# IR_INPUT_POWER.net
KiCad netlist of a schematic drawn in Altium Designer
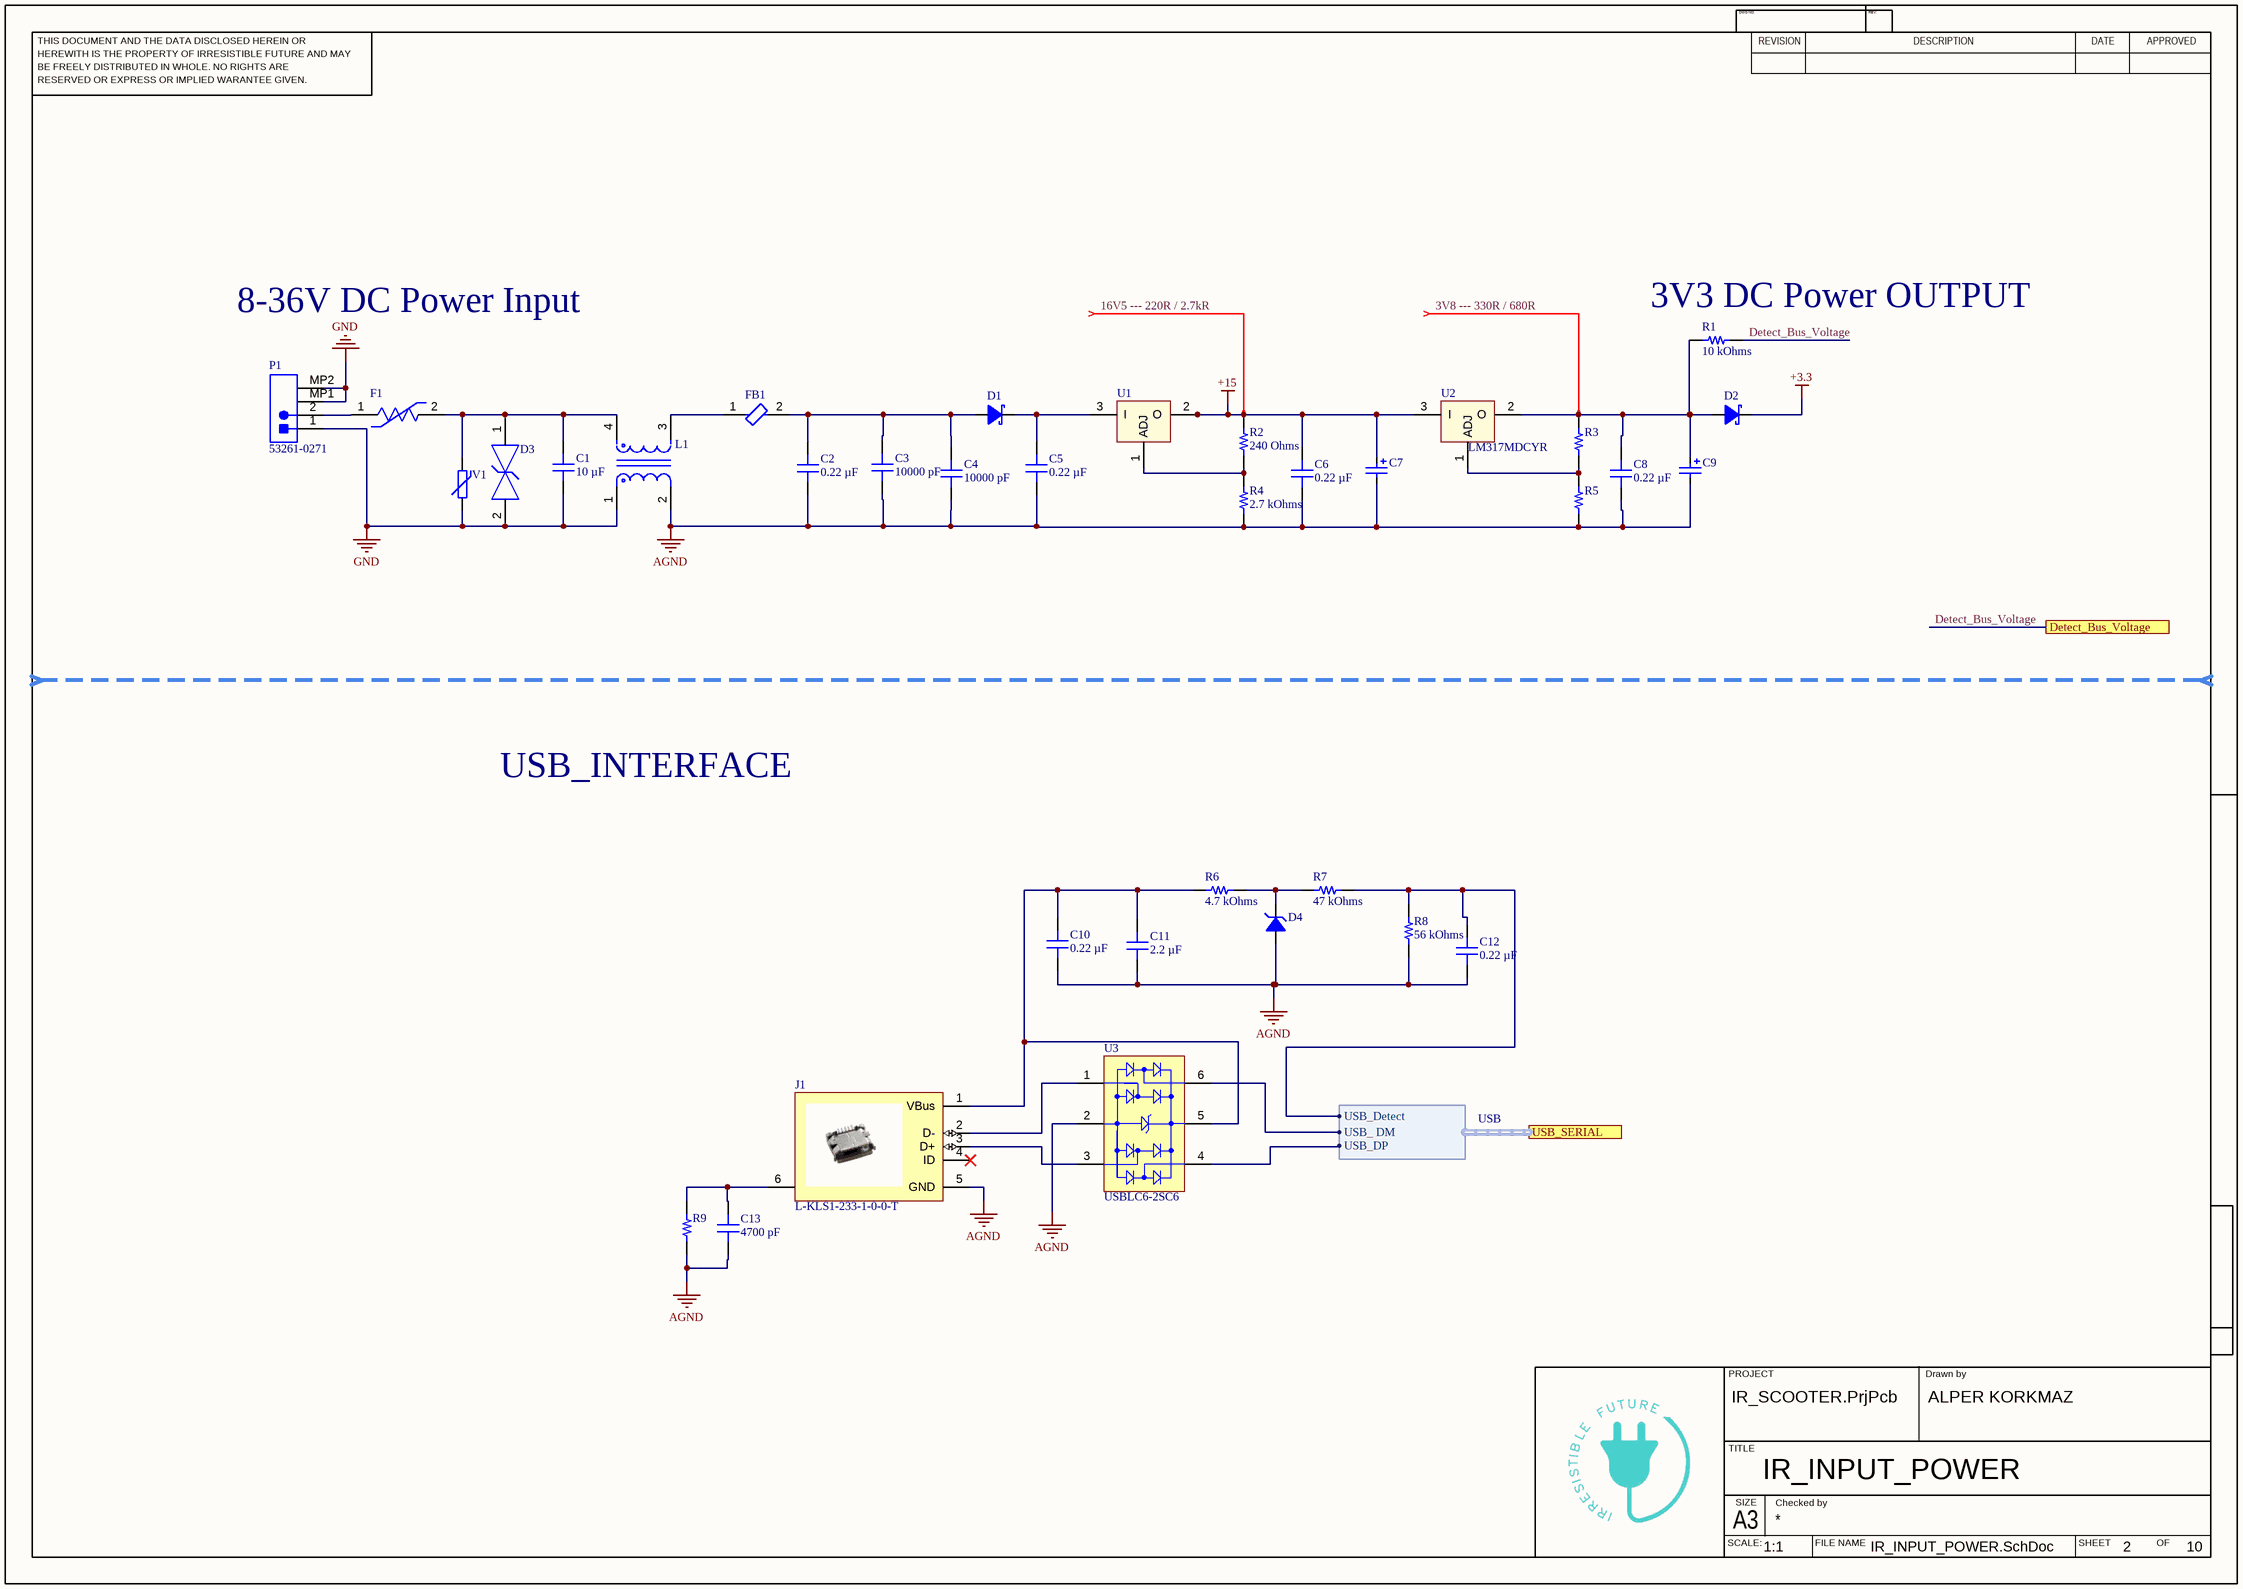
[diagram p0: IR_INPUT_POWER.SchDoc]

(export (version "E")
  (design (tool "Eeschema 10.0.6"))
  (components
    (comp (ref "C1")
      (value "10 µF")
      (footprint "CAP 1206_3216 - 0.8MM")
      (description "CAP CER 10UF 16V X5R 1206")
      (fields (field (name "PART NUMBER") "EMK316BJ106MD-T") (field (name "MANUFACTURER") "Taiyo Yuden"))
      (libsource (lib "Celestial Altium Library - altium_library") (part "Capacitor"))
    )
    (comp (ref "C2")
      (value "0.22 µF")
      (footprint "CAP 0805_2012")
      (description "CAP CER 0.22UF 100V X7R 0805")
      (fields (field (name "PART NUMBER") "HMJ212BB7224KGHT") (field (name "MANUFACTURER") "Taiyo Yuden"))
      (libsource (lib "Celestial Altium Library - altium_library") (part "Capacitor"))
    )
    (comp (ref "C3")
      (value "10000 pF")
      (footprint "CAP 0805_2012")
      (description "CAP CER 0805 10NF 100V X7R")
      (fields (field (name "PART NUMBER") "C0805X103K1RAC3316") (field (name "MANUFACTURER") "KEMET"))
      (libsource (lib "Celestial Altium Library - altium_library") (part "Capacitor"))
    )
    (comp (ref "C4")
      (value "10000 pF")
      (footprint "CAP 0805_2012")
      (description "CAP CER SMD 0805 .01UF X7R 5% 50")
      (fields (field (name "PART NUMBER") "C0805C103J5RAC7210") (field (name "MANUFACTURER") "KEMET"))
      (libsource (lib "Celestial Altium Library - altium_library") (part "Capacitor"))
    )
    (comp (ref "C5")
      (value "0.22 µF")
      (footprint "CAP 0805_2012")
      (description "CAP CER 0.22UF 100V X7R 0805")
      (fields (field (name "PART NUMBER") "HMJ212BB7224KGHT") (field (name "MANUFACTURER") "Taiyo Yuden"))
      (libsource (lib "Celestial Altium Library - altium_library") (part "Capacitor"))
    )
    (comp (ref "C6")
      (value "0.22 µF")
      (footprint "CAP 0805_2012")
      (description "CAP CER 0.22UF 100V X7R 0805")
      (fields (field (name "PART NUMBER") "HMJ212BB7224KGHT") (field (name "MANUFACTURER") "Taiyo Yuden"))
      (libsource (lib "Celestial Altium Library - altium_library") (part "Capacitor"))
    )
    (comp (ref "C7")
      (value "EEE-1VA101XP")
      (footprint "AE_C_R6")
      (description "CAP ALUM 100UF 20% 35V SMD")
      (fields
        (field (name "TOLERANCE") "±20%")
        (field (name "MANUFACTURER") "Panasonic Electronic Components")
      )
      (libsource (lib "Altium_Lib") (part "Capacitor_(Electrolytic)__EEE-1VA101XP"))
    )
    (comp (ref "C8")
      (value "0.22 µF")
      (footprint "CAP 0805_2012")
      (description "CAP CER 0.22UF 100V X7R 0805")
      (fields (field (name "PART NUMBER") "HMJ212BB7224KGHT") (field (name "MANUFACTURER") "Taiyo Yuden"))
      (libsource (lib "Celestial Altium Library - altium_library") (part "Capacitor"))
    )
    (comp (ref "C9")
      (value "EEE-1VA101XP")
      (footprint "AE_C_R6")
      (description "CAP ALUM 100UF 20% 35V SMD")
      (fields
        (field (name "TOLERANCE") "±20%")
        (field (name "MANUFACTURER") "Panasonic Electronic Components")
      )
      (libsource (lib "Altium_Lib") (part "Capacitor_(Electrolytic)__EEE-1VA101XP"))
    )
    (comp (ref "C10")
      (value "0.22 µF")
      (footprint "CAP 0805_2012")
      (description "CAP CER 0.22UF 100V X7R 0805")
      (fields (field (name "PART NUMBER") "HMJ212BB7224KGHT") (field (name "MANUFACTURER") "Taiyo Yuden"))
      (libsource (lib "Celestial Altium Library - altium_library") (part "Capacitor"))
    )
    (comp (ref "C11")
      (value "2.2 µF")
      (footprint "CAP 0805_2012")
      (description "CAP CER 2.2UF 50V X5R 0805")
      (fields
        (field (name "PART NUMBER") "CL21A225KB9LNNC")
        (field (name "MANUFACTURER") "Samsung Electro-Mechanics")
      )
      (libsource (lib "Celestial Altium Library - altium_library") (part "Capacitor"))
    )
    (comp (ref "C12")
      (value "0.22 µF")
      (footprint "CAP 0805_2012")
      (description "CAP CER 0.22UF 100V X7R 0805")
      (fields (field (name "PART NUMBER") "HMJ212BB7224KGHT") (field (name "MANUFACTURER") "Taiyo Yuden"))
      (libsource (lib "Celestial Altium Library - altium_library") (part "Capacitor"))
    )
    (comp (ref "C13")
      (value "4700 pF")
      (footprint "CAP 0805_2012")
      (description "CAP CER 4700PF 50V X7R 0805")
      (fields (field (name "PART NUMBER") "C0805C472K5RACAUTO") (field (name "MANUFACTURER") "KEMET"))
      (libsource (lib "Celestial Altium Library - altium_library") (part "Capacitor"))
    )
    (comp (ref "D1")
      (value "PMEG6020ELRX")
      (footprint "SOD123W")
      (description "DIODE SCHOTTKY 60V 2A CFP3")
      (fields (field (name "MANUFACTURER") "Nexperia"))
      (libsource (lib "Altium_Lib") (part "DIODE_PMEG6020ELRX"))
    )
    (comp (ref "D2")
      (value "PMEG6020ELRX")
      (footprint "SOD123W")
      (description "DIODE SCHOTTKY 60V 2A CFP3")
      (fields (field (name "MANUFACTURER") "Nexperia"))
      (libsource (lib "Altium_Lib") (part "DIODE_PMEG6020ELRX"))
    )
    (comp (ref "D3")
      (value "SMAJ5.0CA-TR")
      (footprint "FP-SMA-MFG")
      (description "TVS DIODE 5V 13.4V SMA")
      (fields
        (field (name "MANUFACTURER") "STMicroelectronics")
        (field (name "OCTOPART") "https://octopart.com/smaj5.0ca-tr-stmicroelectronics-350177")
      )
      (libsource (lib "Altium Content Vault") (part "876f4347bf90aa6f500f43e3cd03972"))
    )
    (comp (ref "D4")
      (value "BZT52C5V6-HE3-08")
      (footprint "SOD123")
      (description "DIODE ZENER 5.6V 410MW SOD123")
      (fields (field (name "MANUFACTURER") "Vishay") (field (name "TOLERANCE") "5%"))
      (libsource (lib "Altium_Lib") (part "DIODE_BZT52C5V6-HE3-08"))
    )
    (comp (ref "F1")
      (value "1812L075/33DR")
      (footprint "FP-1812L075-33DR-MFG")
      (description "PTC RESET FUSE 33V 750MA 1812")
      (libsource (lib "Altium Content Vault") (part "fdf083d5f6389a9a1c4e51137f46658"))
    )
    (comp (ref "FB1")
      (value "BLM21PG220SN1D")
      (footprint "FP-BLM21-0_2-t0_85-e0_5-MFG")
      (description "Chip Ferrite Bead, 0805, 22Ω @ 100MHz, 0.009Ω, 25%, 6A")
      (fields (field (name "TOLERANCE") "25%"))
      (libsource (lib "Altium Content Vault") (part "5f30dd21d616792df468990f7003faa"))
    )
    (comp (ref "J1")
      (value "L-KLS1-233-1-0-0-T")
      (footprint "USB_MICRO_1981584-1")
      (description "Conn Micro USB 2.0 Type AB RCP 5 POS 0.65mm Solder RA SMD 5 Terminal 1 Port T/R")
      (fields (field (name "MANUFACTURER") "KLS Electronic"))
      (libsource (lib "Altium_Lib") (part "USB_Micro_L-KLS1-233-1-0-0-T"))
    )
    (comp (ref "L1")
      (value "DLW5BTM101SQ2L")
      (footprint "FP-DLW5BT-MFG")
      (description "Common Mode Choke, 2020, 100Ω @ 100MHz, 0.013Ω, 6A")
      (fields (field (name "TOLERANCE") "40%"))
      (libsource (lib "Altium Content Vault") (part "7e18bf8fdb9f2485ca2bcdf9073d69f"))
    )
    (comp (ref "P1")
      (value "53261-0271")
      (footprint "MOLX-53261-0271_V")
      (description "PicoBlade(TM) Header, Right Angle, -40 to 85 degC, 2-Pin SMD, RoHS, Tape and Reel")
      (fields (field (name "MANUFACTURER") "Molex"))
      (libsource (lib "Altium Content Vault") (part "CN-1P-2M-R2"))
    )
    (comp (ref "R1")
      (value "10 kOhms")
      (footprint "RES 0603_1608")
      (description "RES 10K OHM 0.1% 1/16W 0603")
      (fields
        (field (name "PART NUMBER") "RNCS0603BKE10K0")
        (field (name "MANUFACTURER") "Stackpole Electronics Inc")
      )
      (libsource (lib "Celestial Altium Library - altium_library") (part "Resistor"))
    )
    (comp (ref "R2")
      (value "240 Ohms")
      (footprint "RES 0603_1608")
      (description "RES SMD 240 OHM 5% 1/4W 0603")
      (fields (field (name "PART NUMBER") "ESR03EZPJ240") (field (name "MANUFACTURER") "Rohm Semiconductor"))
      (libsource (lib "Celestial Altium Library - altium_library") (part "Resistor"))
    )
    (comp (ref "R3")
      (value "330 Ohms")
      (footprint "RES 0603_1608")
      (description "RES SMD 330 OHM 1% 1/5W 0603")
      (fields
        (field (name "PART NUMBER") "CRGH0603F330R")
        (field (name "MANUFACTURER") "TE Connectivity Passive Product")
      )
      (libsource (lib "Celestial Altium Library - altium_library") (part "Resistor"))
    )
    (comp (ref "R4")
      (value "2.7 kOhms")
      (footprint "RES 0603_1608")
      (description "RES 2.7K OHM 1% 1/4W 0603")
      (fields
        (field (name "PART NUMBER") "CRGP0603F2K7")
        (field (name "MANUFACTURER") "TE Connectivity Passive Product")
      )
      (libsource (lib "Celestial Altium Library - altium_library") (part "Resistor"))
    )
    (comp (ref "R5")
      (value "680 Ohms")
      (footprint "RES 0603_1608")
      (description "RES SMD 680 OHM 1% 1/10W 0603")
      (fields (field (name "PART NUMBER") "KTR03EZPF6800") (field (name "MANUFACTURER") "Rohm Semiconductor"))
      (libsource (lib "Celestial Altium Library - altium_library") (part "Resistor"))
    )
    (comp (ref "R6")
      (value "4.7 kOhms")
      (footprint "RES 0603_1608")
      (description "RES SMD 4.7K OHM 0.1% 1/10W 0603")
      (fields
        (field (name "PART NUMBER") "ERA-3AEB472V")
        (field (name "MANUFACTURER") "Panasonic Electronic Components")
      )
      (libsource (lib "Celestial Altium Library - altium_library") (part "Resistor"))
    )
    (comp (ref "R7")
      (value "47 kOhms")
      (footprint "RES 0603_1608")
      (description "RES SMD 47K OHM 5% 1/4W 0603")
      (fields (field (name "PART NUMBER") "RCS060347K0JNEA") (field (name "MANUFACTURER") "Vishay Dale"))
      (libsource (lib "Celestial Altium Library - altium_library") (part "Resistor"))
    )
    (comp (ref "R8")
      (value "56 kOhms")
      (footprint "RES 0603_1608")
      (description "RES SMD 56K OHM 0.1% 1/10W 0603")
      (fields (field (name "PART NUMBER") "RT0603BRD0756KL") (field (name "MANUFACTURER") "Yageo"))
      (libsource (lib "Celestial Altium Library - altium_library") (part "Resistor"))
    )
    (comp (ref "R9")
      (value "1 MOhms")
      (footprint "RES 0603_1608")
      (description "RES SMD 1M OHM 0.1% 1/10W 0603")
      (fields (field (name "PART NUMBER") "RT0603BRD071ML") (field (name "MANUFACTURER") "Yageo"))
      (libsource (lib "Celestial Altium Library - altium_library") (part "Resistor"))
    )
    (comp (ref "U1")
      (value "LM317MDCYR")
      (footprint "SOT-223-4")
      (description "IC REG LINEAR ADJ 0.5A SOT223")
      (fields (field (name "MANUFACTURER") "Texas Instruments"))
      (libsource (lib "Altium_Lib") (part "LM317MDCY"))
    )
    (comp (ref "U2")
      (value "LM317MDCYR")
      (footprint "SOT-223-4")
      (description "IC REG LINEAR ADJ 0.5A SOT223")
      (fields (field (name "MANUFACTURER") "Texas Instruments"))
      (libsource (lib "Altium_Lib") (part "LM317MDCY"))
    )
    (comp (ref "U3")
      (value "USBLC6-2SC6")
      (footprint "STM-SOT23-6L_V")
      (description "Very low capacitance ESD protection, 3.5 pF, -40 to 125 degC, 6-Pin SOT23, RoHS, Tape and Reel")
      (fields (field (name "MANUFACTURER") "STMicroelectronics"))
      (libsource (lib "Altium Content Vault") (part "STM-USB_DVI_HDMIULC6-4SC6X-SOT23-6L"))
    )
    (comp (ref "V1")
      (value "82541250")
      (footprint "V-1206")
      (description "VARISTOR 39V 200A 1206")
      (fields (field (name "MANUFACTURER") "Wurth Electronics Inc."))
      (libsource (lib "Altium101") (part "VARISTOR_82541250"))
    )
  )
  (nets
    (net (code "2") (name "+3.3") (class "Default")
      (node (ref "D2") (pin "1") (pinfunction "K_1") (pintype "passive"))
    )
    (net (code "3") (name "+15") (class "Default")
      (node (ref "C6") (pin "2") (pinfunction "2_2") (pintype "passive"))
      (node (ref "C7") (pin "1") (pinfunction "1_1") (pintype "passive"))
      (node (ref "R2") (pin "2") (pinfunction "2_2") (pintype "passive"))
      (node (ref "U1") (pin "2") (pinfunction "O_2") (pintype "power_in"))
      (node (ref "U2") (pin "3") (pinfunction "I_3") (pintype "power_in"))
    )
    (net (code "4") (name "/Detect_Bus_Voltage") (class "Default")
      (node (ref "R1") (pin "2") (pinfunction "2_2") (pintype "passive"))
    )
    (net (code "5") (name "/USB_ DM") (class "Default")
      (node (ref "U3") (pin "6") (pinfunction "I/O_4_6") (pintype "passive"))
    )
    (net (code "6") (name "/USB_DP") (class "Default")
      (node (ref "U3") (pin "4") (pinfunction "I/O_3_4") (pintype "passive"))
    )
    (net (code "7") (name "/USB_Detect") (class "Default")
      (node (ref "C12") (pin "2") (pinfunction "2_2") (pintype "passive"))
      (node (ref "R7") (pin "2") (pinfunction "2_2") (pintype "passive"))
      (node (ref "R8") (pin "2") (pinfunction "2_2") (pintype "passive"))
    )
    (net (code "9") (name "AGND") (class "Default")
      (node (ref "C10") (pin "1") (pinfunction "1_1") (pintype "passive"))
      (node (ref "C11") (pin "1") (pinfunction "1_1") (pintype "passive"))
      (node (ref "C12") (pin "1") (pinfunction "1_1") (pintype "passive"))
      (node (ref "C13") (pin "1") (pinfunction "1_1") (pintype "passive"))
      (node (ref "C2") (pin "1") (pinfunction "1_1") (pintype "passive"))
      (node (ref "C3") (pin "1") (pinfunction "1_1") (pintype "passive"))
      (node (ref "C4") (pin "1") (pinfunction "1_1") (pintype "passive"))
      (node (ref "C5") (pin "1") (pinfunction "1_1") (pintype "passive"))
      (node (ref "C6") (pin "1") (pinfunction "1_1") (pintype "passive"))
      (node (ref "C7") (pin "2") (pinfunction "2_2") (pintype "passive"))
      (node (ref "C8") (pin "1") (pinfunction "1_1") (pintype "passive"))
      (node (ref "C9") (pin "2") (pinfunction "2_2") (pintype "passive"))
      (node (ref "D4") (pin "1") (pinfunction "T1_1") (pintype "passive"))
      (node (ref "J1") (pin "5") (pinfunction "GND_5") (pintype "passive"))
      (node (ref "L1") (pin "2") (pinfunction "2_2") (pintype "passive"))
      (node (ref "R4") (pin "1") (pinfunction "1_1") (pintype "passive"))
      (node (ref "R5") (pin "1") (pinfunction "1_1") (pintype "passive"))
      (node (ref "R8") (pin "1") (pinfunction "1_1") (pintype "passive"))
      (node (ref "R9") (pin "1") (pinfunction "1_1") (pintype "passive"))
      (node (ref "U3") (pin "2") (pinfunction "GND_2") (pintype "passive"))
    )
    (net (code "10") (name "GND") (class "Default")
      (node (ref "C1") (pin "1") (pinfunction "1_1") (pintype "passive"))
      (node (ref "D3") (pin "2") (pinfunction "2_2") (pintype "passive"))
      (node (ref "L1") (pin "1") (pinfunction "1_1") (pintype "passive"))
      (node (ref "P1") (pin "1") (pinfunction "1_1") (pintype "passive"))
      (node (ref "P1") (pin "MP1") (pinfunction "MP1_MP1") (pintype "passive"))
      (node (ref "P1") (pin "MP2") (pinfunction "MP2_MP2") (pintype "passive"))
      (node (ref "V1") (pin "1") (pinfunction "1_1") (pintype "passive"))
    )
    (net (code "11") (name "Net-(C1-Pad2)") (class "Default")
      (node (ref "C1") (pin "2") (pinfunction "2_2") (pintype "passive"))
      (node (ref "D3") (pin "1") (pinfunction "1_1") (pintype "passive"))
      (node (ref "F1") (pin "2") (pinfunction "2_2") (pintype "passive"))
      (node (ref "L1") (pin "4") (pinfunction "4_4") (pintype "passive"))
      (node (ref "V1") (pin "2") (pinfunction "2_2") (pintype "passive"))
    )
    (net (code "12") (name "Net-(D1-A)") (class "Default")
      (node (ref "C2") (pin "2") (pinfunction "2_2") (pintype "passive"))
      (node (ref "C3") (pin "2") (pinfunction "2_2") (pintype "passive"))
      (node (ref "C4") (pin "2") (pinfunction "2_2") (pintype "passive"))
      (node (ref "D1") (pin "2") (pinfunction "A_2") (pintype "passive"))
      (node (ref "FB1") (pin "2") (pinfunction "2_2") (pintype "passive"))
    )
    (net (code "13") (name "Net-(D1-K)") (class "Default")
      (node (ref "C5") (pin "2") (pinfunction "2_2") (pintype "passive"))
      (node (ref "D1") (pin "1") (pinfunction "K_1") (pintype "passive"))
      (node (ref "U1") (pin "3") (pinfunction "I_3") (pintype "power_in"))
    )
    (net (code "14") (name "Net-(D2-A)") (class "Default")
      (node (ref "C8") (pin "2") (pinfunction "2_2") (pintype "passive"))
      (node (ref "C9") (pin "1") (pinfunction "1_1") (pintype "passive"))
      (node (ref "D2") (pin "2") (pinfunction "A_2") (pintype "passive"))
      (node (ref "R1") (pin "1") (pinfunction "1_1") (pintype "passive"))
      (node (ref "R3") (pin "2") (pinfunction "2_2") (pintype "passive"))
      (node (ref "U2") (pin "2") (pinfunction "O_2") (pintype "power_in"))
    )
    (net (code "15") (name "Net-(D4-T2)") (class "Default")
      (node (ref "D4") (pin "2") (pinfunction "T2_2") (pintype "passive"))
      (node (ref "R6") (pin "2") (pinfunction "2_2") (pintype "passive"))
      (node (ref "R7") (pin "1") (pinfunction "1_1") (pintype "passive"))
    )
    (net (code "16") (name "Net-(F1-Pad1)") (class "Default")
      (node (ref "F1") (pin "1") (pinfunction "1_1") (pintype "passive"))
      (node (ref "P1") (pin "2") (pinfunction "2_2") (pintype "passive"))
    )
    (net (code "17") (name "Net-(FB1-Pad1)") (class "Default")
      (node (ref "FB1") (pin "1") (pinfunction "1_1") (pintype "passive"))
      (node (ref "L1") (pin "3") (pinfunction "3_3") (pintype "passive"))
    )
    (net (code "18") (name "Net-(J1-D+)") (class "Default")
      (node (ref "J1") (pin "3") (pinfunction "D+_3") (pintype "bidirectional"))
      (node (ref "U3") (pin "3") (pinfunction "I/O_2_3") (pintype "passive"))
    )
    (net (code "19") (name "Net-(J1-D-)") (class "Default")
      (node (ref "J1") (pin "2") (pinfunction "D-_2") (pintype "bidirectional"))
      (node (ref "U3") (pin "1") (pinfunction "I/O_1_1") (pintype "passive"))
    )
    (net (code "20") (name "Net-(J1-Shield)") (class "Default")
      (node (ref "C13") (pin "2") (pinfunction "2_2") (pintype "passive"))
      (node (ref "J1") (pin "6") (pinfunction "Shield_6") (pintype "passive"))
      (node (ref "R9") (pin "2") (pinfunction "2_2") (pintype "passive"))
    )
    (net (code "21") (name "Net-(J1-VBus)") (class "Default")
      (node (ref "C10") (pin "2") (pinfunction "2_2") (pintype "passive"))
      (node (ref "C11") (pin "2") (pinfunction "2_2") (pintype "passive"))
      (node (ref "J1") (pin "1") (pinfunction "VBus_1") (pintype "power_in"))
      (node (ref "R6") (pin "1") (pinfunction "1_1") (pintype "passive"))
      (node (ref "U3") (pin "5") (pinfunction "VBUS_5") (pintype "passive"))
    )
    (net (code "22") (name "Net-(U1-ADJ)") (class "Default")
      (node (ref "R2") (pin "1") (pinfunction "1_1") (pintype "passive"))
      (node (ref "R4") (pin "2") (pinfunction "2_2") (pintype "passive"))
      (node (ref "U1") (pin "1") (pinfunction "ADJ_1") (pintype "power_in"))
    )
    (net (code "23") (name "Net-(U2-ADJ)") (class "Default")
      (node (ref "R3") (pin "1") (pinfunction "1_1") (pintype "passive"))
      (node (ref "R5") (pin "2") (pinfunction "2_2") (pintype "passive"))
      (node (ref "U2") (pin "1") (pinfunction "ADJ_1") (pintype "power_in"))
    )
    (net (code "24") (name "unconnected-(J1-ID-Pad4)") (class "Default")
      (node (ref "J1") (pin "4") (pinfunction "ID_4") (pintype "power_in+no_connect"))
    )
  )
)
